# RHD2132_lvds_headstage_3_1.net
KiCad netlist of a schematic drawn in EAGLE
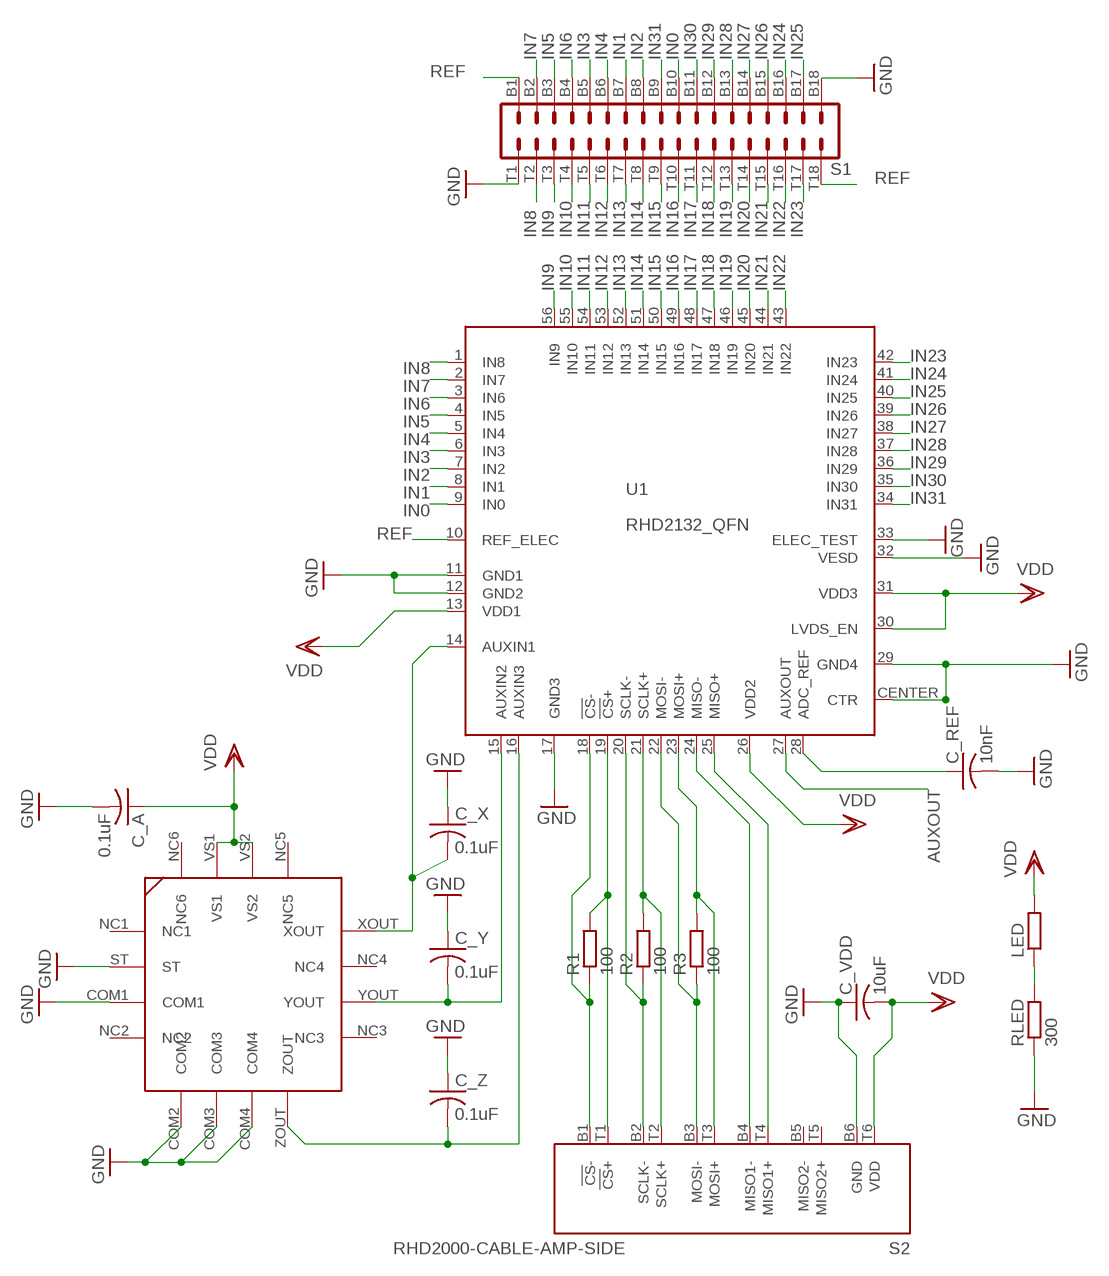
[diagram p0: schematic, sheet 1]

(export (version "E")
  (design (tool "Eeschema 10.0.6"))
  (components
    (comp (ref "C_A")
      (value "0.1uF")
      (footprint "eagle-import:C0402K")
      (libsource (lib "eagle-import") (part "C-USC0402K"))
    )
    (comp (ref "C_REF")
      (value "10nF")
      (footprint "eagle-import:C0402K")
      (libsource (lib "eagle-import") (part "C-USC0402K"))
    )
    (comp (ref "C_VDD")
      (value "10uF")
      (footprint "eagle-import:C0402K")
      (libsource (lib "eagle-import") (part "C-USC0402K"))
    )
    (comp (ref "C_X")
      (value "0.1uF")
      (footprint "eagle-import:C0402K")
      (libsource (lib "eagle-import") (part "C-USC0402K"))
    )
    (comp (ref "C_Y")
      (value "0.1uF")
      (footprint "eagle-import:C0402K")
      (libsource (lib "eagle-import") (part "C-USC0402K"))
    )
    (comp (ref "C_Z")
      (value "0.1uF")
      (footprint "eagle-import:C0402K")
      (libsource (lib "eagle-import") (part "C-USC0402K"))
    )
    (comp (ref "LED")
      (value "R-EU_R0402")
      (footprint "eagle-import:R0402")
      (libsource (lib "eagle-import") (part "R-EU_R0402"))
    )
    (comp (ref "R1")
      (value "100")
      (footprint "eagle-import:R0402")
      (libsource (lib "eagle-import") (part "R-EU_R0402"))
    )
    (comp (ref "R2")
      (value "100")
      (footprint "eagle-import:R0402")
      (libsource (lib "eagle-import") (part "R-EU_R0402"))
    )
    (comp (ref "R3")
      (value "100")
      (footprint "eagle-import:R0402")
      (libsource (lib "eagle-import") (part "R-EU_R0402"))
    )
    (comp (ref "RLED")
      (value "300")
      (footprint "eagle-import:R0402")
      (libsource (lib "eagle-import") (part "R-EU_R0402"))
    )
    (comp (ref "S1")
      (value "OMNETICS_A79025")
      (footprint "eagle-import:OMNETICS_A79025")
      (libsource (lib "eagle-import") (part "OMNETICS_A79025"))
    )
    (comp (ref "S2")
      (value "RHD2000-CABLE-AMP-SIDE")
      (footprint "eagle-import:OMNETICS_PZN-12-AA")
      (libsource (lib "eagle-import") (part "RHD2000-CABLE-AMP-SIDE"))
    )
    (comp (ref "U$1")
      (value "ADXL335")
      (footprint "eagle-import:ADXL335")
      (libsource (lib "eagle-import") (part "ADXL335"))
    )
    (comp (ref "U1")
      (value "RHD2132_QFN")
      (footprint "eagle-import:QFN56_8_X_8_LARGE")
      (libsource (lib "eagle-import") (part "RHD2132_QFN"))
    )
  )
  (nets
    (net (code "1") (name "/AUXOUT") (class "Default")
      (node (ref "U1") (pin "27") (pinfunction "AUXOUT_27") (pintype "tri_state"))
    )
    (net (code "2") (name "/IN0") (class "Default")
      (node (ref "S1") (pin "B10") (pinfunction "B10_B10") (pintype "passive"))
      (node (ref "U1") (pin "9") (pinfunction "IN0_9") (pintype "input"))
    )
    (net (code "3") (name "/IN1") (class "Default")
      (node (ref "S1") (pin "B7") (pinfunction "B7_B7") (pintype "passive"))
      (node (ref "U1") (pin "8") (pinfunction "IN1_8") (pintype "input"))
    )
    (net (code "4") (name "/IN2") (class "Default")
      (node (ref "S1") (pin "B8") (pinfunction "B8_B8") (pintype "passive"))
      (node (ref "U1") (pin "7") (pinfunction "IN2_7") (pintype "input"))
    )
    (net (code "5") (name "/IN3") (class "Default")
      (node (ref "S1") (pin "B5") (pinfunction "B5_B5") (pintype "passive"))
      (node (ref "U1") (pin "6") (pinfunction "IN3_6") (pintype "input"))
    )
    (net (code "6") (name "/IN4") (class "Default")
      (node (ref "S1") (pin "B6") (pinfunction "B6_B6") (pintype "passive"))
      (node (ref "U1") (pin "5") (pinfunction "IN4_5") (pintype "input"))
    )
    (net (code "7") (name "/IN5") (class "Default")
      (node (ref "S1") (pin "B3") (pinfunction "B3_B3") (pintype "passive"))
      (node (ref "U1") (pin "4") (pinfunction "IN5_4") (pintype "input"))
    )
    (net (code "8") (name "/IN6") (class "Default")
      (node (ref "S1") (pin "B4") (pinfunction "B4_B4") (pintype "passive"))
      (node (ref "U1") (pin "3") (pinfunction "IN6_3") (pintype "input"))
    )
    (net (code "9") (name "/IN7") (class "Default")
      (node (ref "S1") (pin "B2") (pinfunction "B2_B2") (pintype "passive"))
      (node (ref "U1") (pin "2") (pinfunction "IN7_2") (pintype "input"))
    )
    (net (code "10") (name "/IN8") (class "Default")
      (node (ref "S1") (pin "T2") (pinfunction "T2_T2") (pintype "passive"))
      (node (ref "U1") (pin "1") (pinfunction "IN8_1") (pintype "input"))
    )
    (net (code "11") (name "/IN9") (class "Default")
      (node (ref "S1") (pin "T3") (pinfunction "T3_T3") (pintype "passive"))
      (node (ref "U1") (pin "56") (pinfunction "IN9_56") (pintype "input"))
    )
    (net (code "12") (name "/IN10") (class "Default")
      (node (ref "S1") (pin "T4") (pinfunction "T4_T4") (pintype "passive"))
      (node (ref "U1") (pin "55") (pinfunction "IN10_55") (pintype "input"))
    )
    (net (code "13") (name "/IN11") (class "Default")
      (node (ref "S1") (pin "T5") (pinfunction "T5_T5") (pintype "passive"))
      (node (ref "U1") (pin "54") (pinfunction "IN11_54") (pintype "input"))
    )
    (net (code "14") (name "/IN12") (class "Default")
      (node (ref "S1") (pin "T6") (pinfunction "T6_T6") (pintype "passive"))
      (node (ref "U1") (pin "53") (pinfunction "IN12_53") (pintype "input"))
    )
    (net (code "15") (name "/IN13") (class "Default")
      (node (ref "S1") (pin "T7") (pinfunction "T7_T7") (pintype "passive"))
      (node (ref "U1") (pin "52") (pinfunction "IN13_52") (pintype "input"))
    )
    (net (code "16") (name "/IN14") (class "Default")
      (node (ref "S1") (pin "T8") (pinfunction "T8_T8") (pintype "passive"))
      (node (ref "U1") (pin "51") (pinfunction "IN14_51") (pintype "input"))
    )
    (net (code "17") (name "/IN15") (class "Default")
      (node (ref "S1") (pin "T9") (pinfunction "T9_T9") (pintype "passive"))
      (node (ref "U1") (pin "50") (pinfunction "IN15_50") (pintype "input"))
    )
    (net (code "18") (name "/IN16") (class "Default")
      (node (ref "S1") (pin "T10") (pinfunction "T10_T10") (pintype "passive"))
      (node (ref "U1") (pin "49") (pinfunction "IN16_49") (pintype "input"))
    )
    (net (code "19") (name "/IN17") (class "Default")
      (node (ref "S1") (pin "T11") (pinfunction "T11_T11") (pintype "passive"))
      (node (ref "U1") (pin "48") (pinfunction "IN17_48") (pintype "input"))
    )
    (net (code "20") (name "/IN18") (class "Default")
      (node (ref "S1") (pin "T12") (pinfunction "T12_T12") (pintype "passive"))
      (node (ref "U1") (pin "47") (pinfunction "IN18_47") (pintype "input"))
    )
    (net (code "21") (name "/IN19") (class "Default")
      (node (ref "S1") (pin "T13") (pinfunction "T13_T13") (pintype "passive"))
      (node (ref "U1") (pin "46") (pinfunction "IN19_46") (pintype "input"))
    )
    (net (code "22") (name "/IN20") (class "Default")
      (node (ref "S1") (pin "T14") (pinfunction "T14_T14") (pintype "passive"))
      (node (ref "U1") (pin "45") (pinfunction "IN20_45") (pintype "input"))
    )
    (net (code "23") (name "/IN21") (class "Default")
      (node (ref "S1") (pin "T15") (pinfunction "T15_T15") (pintype "passive"))
      (node (ref "U1") (pin "44") (pinfunction "IN21_44") (pintype "input"))
    )
    (net (code "24") (name "/IN22") (class "Default")
      (node (ref "S1") (pin "T16") (pinfunction "T16_T16") (pintype "passive"))
      (node (ref "U1") (pin "43") (pinfunction "IN22_43") (pintype "input"))
    )
    (net (code "25") (name "/IN23") (class "Default")
      (node (ref "S1") (pin "T17") (pinfunction "T17_T17") (pintype "passive"))
      (node (ref "U1") (pin "42") (pinfunction "IN23_42") (pintype "input"))
    )
    (net (code "26") (name "/IN24") (class "Default")
      (node (ref "S1") (pin "B16") (pinfunction "B16_B16") (pintype "passive"))
      (node (ref "U1") (pin "41") (pinfunction "IN24_41") (pintype "input"))
    )
    (net (code "27") (name "/IN25") (class "Default")
      (node (ref "S1") (pin "B17") (pinfunction "B17_B17") (pintype "passive"))
      (node (ref "U1") (pin "40") (pinfunction "IN25_40") (pintype "input"))
    )
    (net (code "28") (name "/IN26") (class "Default")
      (node (ref "S1") (pin "B15") (pinfunction "B15_B15") (pintype "passive"))
      (node (ref "U1") (pin "39") (pinfunction "IN26_39") (pintype "input"))
    )
    (net (code "29") (name "/IN27") (class "Default")
      (node (ref "S1") (pin "B14") (pinfunction "B14_B14") (pintype "passive"))
      (node (ref "U1") (pin "38") (pinfunction "IN27_38") (pintype "input"))
    )
    (net (code "30") (name "/IN28") (class "Default")
      (node (ref "S1") (pin "B13") (pinfunction "B13_B13") (pintype "passive"))
      (node (ref "U1") (pin "37") (pinfunction "IN28_37") (pintype "input"))
    )
    (net (code "31") (name "/IN29") (class "Default")
      (node (ref "S1") (pin "B12") (pinfunction "B12_B12") (pintype "passive"))
      (node (ref "U1") (pin "36") (pinfunction "IN29_36") (pintype "input"))
    )
    (net (code "32") (name "/IN30") (class "Default")
      (node (ref "S1") (pin "B11") (pinfunction "B11_B11") (pintype "passive"))
      (node (ref "U1") (pin "35") (pinfunction "IN30_35") (pintype "input"))
    )
    (net (code "33") (name "/IN31") (class "Default")
      (node (ref "S1") (pin "B9") (pinfunction "B9_B9") (pintype "passive"))
      (node (ref "U1") (pin "34") (pinfunction "IN31_34") (pintype "input"))
    )
    (net (code "34") (name "/REF") (class "Default")
      (node (ref "S1") (pin "B1") (pinfunction "B1_B1") (pintype "passive"))
      (node (ref "S1") (pin "T18") (pinfunction "T18_T18") (pintype "passive"))
      (node (ref "U1") (pin "10") (pinfunction "REF_ELEC_10") (pintype "input"))
    )
    (net (code "35") (name "GND") (class "Default")
      (node (ref "C_A") (pin "2") (pinfunction "2_2") (pintype "passive"))
      (node (ref "C_REF") (pin "2") (pinfunction "2_2") (pintype "passive"))
      (node (ref "C_VDD") (pin "1") (pinfunction "1_1") (pintype "passive"))
      (node (ref "C_X") (pin "1") (pinfunction "1_1") (pintype "passive"))
      (node (ref "C_Y") (pin "1") (pinfunction "1_1") (pintype "passive"))
      (node (ref "C_Z") (pin "1") (pinfunction "1_1") (pintype "passive"))
      (node (ref "RLED") (pin "1") (pinfunction "1_1") (pintype "passive"))
      (node (ref "S1") (pin "B18") (pinfunction "B18_B18") (pintype "passive"))
      (node (ref "S1") (pin "T1") (pinfunction "T1_T1") (pintype "passive"))
      (node (ref "S2") (pin "B6") (pinfunction "GND_B6") (pintype "power_in"))
      (node (ref "U$1") (pin "COM1") (pinfunction "COM1_COM1") (pintype "bidirectional"))
      (node (ref "U$1") (pin "COM2") (pinfunction "COM2_COM2") (pintype "bidirectional"))
      (node (ref "U$1") (pin "COM3") (pinfunction "COM3_COM3") (pintype "bidirectional"))
      (node (ref "U$1") (pin "COM4") (pinfunction "COM4_COM4") (pintype "bidirectional"))
      (node (ref "U$1") (pin "ST") (pinfunction "ST_ST") (pintype "bidirectional"))
      (node (ref "U1") (pin "11") (pinfunction "GND1_11") (pintype "power_in"))
      (node (ref "U1") (pin "12") (pinfunction "GND2_12") (pintype "power_in"))
      (node (ref "U1") (pin "17") (pinfunction "GND3_17") (pintype "power_in"))
      (node (ref "U1") (pin "29") (pinfunction "GND4_29") (pintype "power_in"))
      (node (ref "U1") (pin "32") (pinfunction "VESD_32") (pintype "power_in"))
      (node (ref "U1") (pin "33") (pinfunction "ELEC_TEST_33") (pintype "input"))
      (node (ref "U1") (pin "CENTER") (pinfunction "CTR_CENTER") (pintype "power_in"))
    )
    (net (code "36") (name "Net-(LED-Pad1)") (class "Default")
      (node (ref "LED") (pin "1") (pinfunction "1_1") (pintype "passive"))
      (node (ref "RLED") (pin "2") (pinfunction "2_2") (pintype "passive"))
    )
    (net (code "37") (name "Net-(S2-MISO1+)") (class "Default")
      (node (ref "S2") (pin "T4") (pinfunction "MISO1+_T4") (pintype "bidirectional"))
      (node (ref "U1") (pin "25") (pinfunction "MISO+_25") (pintype "output"))
    )
    (net (code "38") (name "Net-(S2-MISO1-)") (class "Default")
      (node (ref "S2") (pin "B4") (pinfunction "MISO1-_B4") (pintype "bidirectional"))
      (node (ref "U1") (pin "24") (pinfunction "MISO-_24") (pintype "output"))
    )
    (net (code "39") (name "Net-(S2-MOSI+)") (class "Default")
      (node (ref "R3") (pin "2") (pinfunction "2_2") (pintype "passive"))
      (node (ref "S2") (pin "T3") (pinfunction "MOSI+_T3") (pintype "bidirectional"))
      (node (ref "U1") (pin "23") (pinfunction "MOSI+_23") (pintype "input"))
    )
    (net (code "40") (name "Net-(S2-MOSI-)") (class "Default")
      (node (ref "R3") (pin "1") (pinfunction "1_1") (pintype "passive"))
      (node (ref "S2") (pin "B3") (pinfunction "MOSI-_B3") (pintype "bidirectional"))
      (node (ref "U1") (pin "22") (pinfunction "MOSI-_22") (pintype "input"))
    )
    (net (code "41") (name "Net-(S2-SCLK+)") (class "Default")
      (node (ref "R2") (pin "2") (pinfunction "2_2") (pintype "passive"))
      (node (ref "S2") (pin "T2") (pinfunction "SCLK+_T2") (pintype "bidirectional"))
      (node (ref "U1") (pin "21") (pinfunction "SCLK+_21") (pintype "input"))
    )
    (net (code "42") (name "Net-(S2-SCLK-)") (class "Default")
      (node (ref "R2") (pin "1") (pinfunction "1_1") (pintype "passive"))
      (node (ref "S2") (pin "B2") (pinfunction "SCLK-_B2") (pintype "bidirectional"))
      (node (ref "U1") (pin "20") (pinfunction "SCLK-_20") (pintype "input"))
    )
    (net (code "43") (name "Net-(S2-~{CS}+)") (class "Default")
      (node (ref "R1") (pin "2") (pinfunction "2_2") (pintype "passive"))
      (node (ref "S2") (pin "T1") (pinfunction "~{CS}+_T1") (pintype "bidirectional"))
      (node (ref "U1") (pin "19") (pinfunction "~{CS}+_19") (pintype "input"))
    )
    (net (code "44") (name "Net-(S2-~{CS}-)") (class "Default")
      (node (ref "R1") (pin "1") (pinfunction "1_1") (pintype "passive"))
      (node (ref "S2") (pin "B1") (pinfunction "~{CS}-_B1") (pintype "bidirectional"))
      (node (ref "U1") (pin "18") (pinfunction "~{CS}-_18") (pintype "input"))
    )
    (net (code "45") (name "Net-(U1-ADC_REF)") (class "Default")
      (node (ref "C_REF") (pin "1") (pinfunction "1_1") (pintype "passive"))
      (node (ref "U1") (pin "28") (pinfunction "ADC_REF_28") (pintype "passive"))
    )
    (net (code "46") (name "Net-(U1-AUXIN1)") (class "Default")
      (node (ref "C_X") (pin "2") (pinfunction "2_2") (pintype "passive"))
      (node (ref "U$1") (pin "XOUT") (pinfunction "XOUT_XOUT") (pintype "bidirectional"))
      (node (ref "U1") (pin "14") (pinfunction "AUXIN1_14") (pintype "input"))
    )
    (net (code "47") (name "Net-(U1-AUXIN2)") (class "Default")
      (node (ref "C_Y") (pin "2") (pinfunction "2_2") (pintype "passive"))
      (node (ref "U$1") (pin "YOUT") (pinfunction "YOUT_YOUT") (pintype "bidirectional"))
      (node (ref "U1") (pin "15") (pinfunction "AUXIN2_15") (pintype "input"))
    )
    (net (code "48") (name "Net-(U1-AUXIN3)") (class "Default")
      (node (ref "C_Z") (pin "2") (pinfunction "2_2") (pintype "passive"))
      (node (ref "U$1") (pin "ZOUT") (pinfunction "ZOUT_ZOUT") (pintype "bidirectional"))
      (node (ref "U1") (pin "16") (pinfunction "AUXIN3_16") (pintype "input"))
    )
    (net (code "49") (name "VDD") (class "Default")
      (node (ref "C_A") (pin "1") (pinfunction "1_1") (pintype "passive"))
      (node (ref "C_VDD") (pin "2") (pinfunction "2_2") (pintype "passive"))
      (node (ref "LED") (pin "2") (pinfunction "2_2") (pintype "passive"))
      (node (ref "S2") (pin "T6") (pinfunction "VDD_T6") (pintype "bidirectional"))
      (node (ref "U$1") (pin "VS1") (pinfunction "VS1_VS1") (pintype "bidirectional"))
      (node (ref "U$1") (pin "VS2") (pinfunction "VS2_VS2") (pintype "bidirectional"))
      (node (ref "U1") (pin "13") (pinfunction "VDD1_13") (pintype "power_in"))
      (node (ref "U1") (pin "26") (pinfunction "VDD2_26") (pintype "power_in"))
      (node (ref "U1") (pin "30") (pinfunction "LVDS_EN_30") (pintype "input"))
      (node (ref "U1") (pin "31") (pinfunction "VDD3_31") (pintype "power_in"))
    )
    (net (code "50") (name "unconnected-(S2-MISO2+-PadT5)") (class "Default")
      (node (ref "S2") (pin "T5") (pinfunction "MISO2+_T5") (pintype "bidirectional"))
    )
    (net (code "51") (name "unconnected-(S2-MISO2--PadB5)") (class "Default")
      (node (ref "S2") (pin "B5") (pinfunction "MISO2-_B5") (pintype "bidirectional"))
    )
    (net (code "52") (name "unconnected-(U$1-PadNC1)") (class "Default")
      (node (ref "U$1") (pin "NC1") (pinfunction "NC1_NC1") (pintype "bidirectional"))
    )
    (net (code "53") (name "unconnected-(U$1-PadNC2)") (class "Default")
      (node (ref "U$1") (pin "NC2") (pinfunction "NC2_NC2") (pintype "bidirectional"))
    )
    (net (code "54") (name "unconnected-(U$1-PadNC3)") (class "Default")
      (node (ref "U$1") (pin "NC3") (pinfunction "NC3_NC3") (pintype "bidirectional"))
    )
    (net (code "55") (name "unconnected-(U$1-PadNC4)") (class "Default")
      (node (ref "U$1") (pin "NC4") (pinfunction "NC4_NC4") (pintype "bidirectional"))
    )
    (net (code "56") (name "unconnected-(U$1-PadNC5)") (class "Default")
      (node (ref "U$1") (pin "NC5") (pinfunction "NC5_NC5") (pintype "bidirectional"))
    )
    (net (code "57") (name "unconnected-(U$1-PadNC6)") (class "Default")
      (node (ref "U$1") (pin "NC6") (pinfunction "NC6_NC6") (pintype "bidirectional"))
    )
  )
)
